# Downloader.net
KiCad netlist of a schematic drawn in Altium Designer
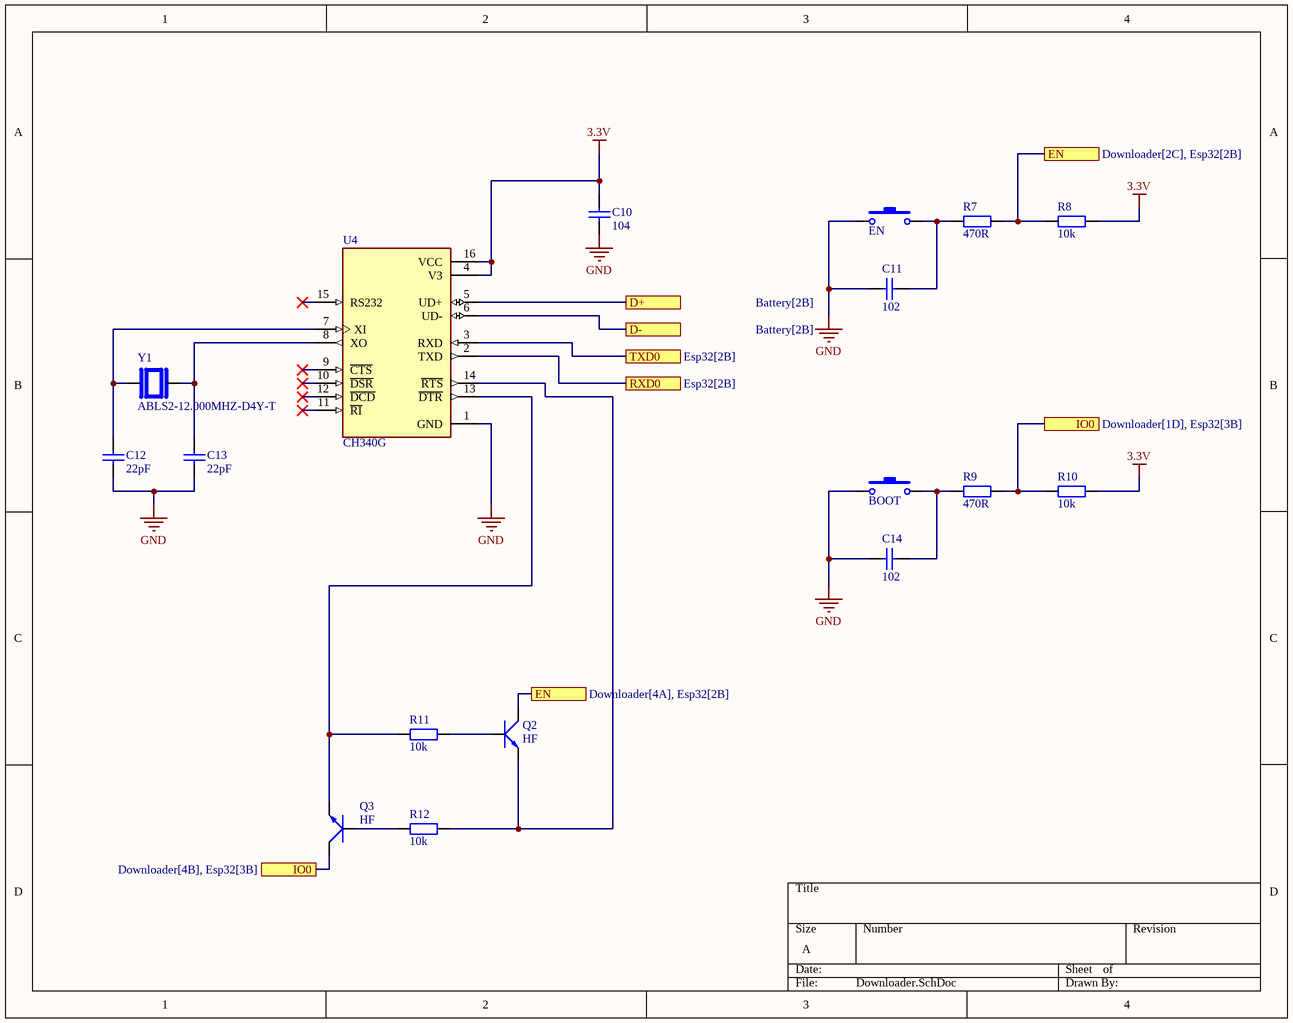
[diagram p0: Downloader.SchDoc]

(export (version "E")
  (design (tool "Eeschema 10.0.6"))
  (components
    (comp (ref "BOOT")
      (value "Nut Nhan 2 Chan SMD 3x6x2.5")
      (footprint "Nut Nhan 2 Chan SMD 3x6x2.5")
      (libsource (lib "Altium_Lib_by_KhueNguyenCreator") (part "Nut Nhan 2 Chan SMD 3x6x2.5"))
    )
    (comp (ref "C10")
      (value "104")
      (footprint "tu 0805")
      (description "Dán")
      (libsource (lib "Altium_Lib_by_KhueNguyenCreator") (part "Tu 0805 104 50V 10%"))
    )
    (comp (ref "C11")
      (value "102")
      (footprint "tu 0805")
      (description "Dán")
      (libsource (lib "Altium_Lib_by_KhueNguyenCreator") (part "Tu 0805 102 50V 10%"))
    )
    (comp (ref "C12")
      (value "22pF")
      (footprint "tu 0805")
      (description "Dán")
      (libsource (lib "Altium_Lib_by_KhueNguyenCreator") (part "Tu 0805 22pF 50V 10%"))
    )
    (comp (ref "C13")
      (value "22pF")
      (footprint "tu 0805")
      (description "Dán")
      (libsource (lib "Altium_Lib_by_KhueNguyenCreator") (part "Tu 0805 22pF 50V 10%"))
    )
    (comp (ref "C14")
      (value "102")
      (footprint "tu 0805")
      (description "Dán")
      (libsource (lib "Altium_Lib_by_KhueNguyenCreator") (part "Tu 0805 102 50V 10%"))
    )
    (comp (ref "EN")
      (value "Nut Nhan 2 Chan SMD 3x6x2.5")
      (footprint "Nut Nhan 2 Chan SMD 3x6x2.5")
      (libsource (lib "Altium_Lib_by_KhueNguyenCreator") (part "Nut Nhan 2 Chan SMD 3x6x2.5"))
    )
    (comp (ref "Q2")
      (value "HF")
      (footprint "SOT-23")
      (description "SOT-23")
      (libsource (lib "Altium_Lib_by_KhueNguyenCreator") (part "Trans C1815 HF SMD"))
    )
    (comp (ref "Q3")
      (value "HF")
      (footprint "SOT-23")
      (description "SOT-23")
      (libsource (lib "Altium_Lib_by_KhueNguyenCreator") (part "Trans C1815 HF SMD"))
    )
    (comp (ref "R7")
      (value "470R")
      (footprint "Tro SMD 0805")
      (description "Dán")
      (libsource (lib "Altium_Lib_by_KhueNguyenCreator") (part "Tro 0805 5% 470R"))
    )
    (comp (ref "R8")
      (value "10k")
      (footprint "tro smd 0805")
      (description "Dán")
      (libsource (lib "Altium_Lib_by_KhueNguyenCreator") (part "Tro 0805 5% 10k"))
    )
    (comp (ref "R9")
      (value "470R")
      (footprint "Tro SMD 0805")
      (description "Dán")
      (libsource (lib "Altium_Lib_by_KhueNguyenCreator") (part "Tro 0805 5% 470R"))
    )
    (comp (ref "R10")
      (value "10k")
      (footprint "tro smd 0805")
      (description "Dán")
      (libsource (lib "Altium_Lib_by_KhueNguyenCreator") (part "Tro 0805 5% 10k"))
    )
    (comp (ref "R11")
      (value "10k")
      (footprint "tro smd 0805")
      (description "Dán")
      (libsource (lib "Altium_Lib_by_KhueNguyenCreator") (part "Tro 0805 5% 10k"))
    )
    (comp (ref "R12")
      (value "10k")
      (footprint "tro smd 0805")
      (description "Dán")
      (libsource (lib "Altium_Lib_by_KhueNguyenCreator") (part "Tro 0805 5% 10k"))
    )
    (comp (ref "U4")
      (value "CH340G")
      (footprint "SOIC127P600X180-16N")
      (description "USB Interface Integrated Circuit")
      (fields (field (name "MP") "Ch340G") (field (name "MF") "WCH"))
      (libsource (lib "CH340G") (part "CH340G"))
    )
    (comp (ref "Y1")
      (value "ABLS2-12.000MHZ-D4Y-T")
      (footprint "XTAL_ABLS2-12.000MHZ-D4Y-T")
      (description "HC/49US (AT49) LOW PROFILE SURFACE MOUNT MICROPROCESSOR CRYSTAL")
      (fields (field (name "MF") "Abracon"))
      (libsource (lib "ABLS2-12.000MHZ-D4Y-T") (part "ABLS2-12.000MHZ-D4Y-T"))
    )
  )
  (nets
    (net (code "1") (name "/D+") (class "Default")
      (node (ref "U4") (pin "5") (pinfunction "UD+_5") (pintype "bidirectional"))
    )
    (net (code "2") (name "/D-") (class "Default")
      (node (ref "U4") (pin "6") (pinfunction "UD-_6") (pintype "bidirectional"))
    )
    (net (code "3") (name "/EN") (class "Default")
      (node (ref "Q2") (pin "3") (pinfunction "C_3") (pintype "passive"))
      (node (ref "R7") (pin "2") (pinfunction "2_2") (pintype "passive"))
      (node (ref "R8") (pin "1") (pinfunction "1_1") (pintype "passive"))
    )
    (net (code "4") (name "/IO0") (class "Default")
      (node (ref "Q3") (pin "3") (pinfunction "C_3") (pintype "passive"))
      (node (ref "R10") (pin "1") (pinfunction "1_1") (pintype "passive"))
      (node (ref "R9") (pin "2") (pinfunction "2_2") (pintype "passive"))
    )
    (net (code "5") (name "/RXD0") (class "Default")
      (node (ref "U4") (pin "2") (pinfunction "TXD_2") (pintype "output"))
    )
    (net (code "6") (name "/TXD0") (class "Default")
      (node (ref "U4") (pin "3") (pinfunction "RXD_3") (pintype "input"))
    )
    (net (code "7") (name "3.3V") (class "Default")
      (node (ref "C10") (pin "1") (pinfunction "1_1") (pintype "passive"))
      (node (ref "R10") (pin "2") (pinfunction "2_2") (pintype "passive"))
      (node (ref "R8") (pin "2") (pinfunction "2_2") (pintype "passive"))
      (node (ref "U4") (pin "16") (pinfunction "VCC_16") (pintype "power_in"))
      (node (ref "U4") (pin "4") (pinfunction "V3_4") (pintype "power_in"))
    )
    (net (code "8") (name "GND") (class "Default")
      (node (ref "BOOT") (pin "1") (pinfunction "1_1") (pintype "passive"))
      (node (ref "C10") (pin "2") (pinfunction "2_2") (pintype "passive"))
      (node (ref "C11") (pin "2") (pinfunction "2_2") (pintype "passive"))
      (node (ref "C12") (pin "2") (pinfunction "2_2") (pintype "passive"))
      (node (ref "C13") (pin "2") (pinfunction "2_2") (pintype "passive"))
      (node (ref "C14") (pin "2") (pinfunction "2_2") (pintype "passive"))
      (node (ref "EN") (pin "1") (pinfunction "1_1") (pintype "passive"))
      (node (ref "U4") (pin "1") (pinfunction "GND_1") (pintype "power_in"))
    )
    (net (code "9") (name "Net-(BOOT-Pad2)") (class "Default")
      (node (ref "BOOT") (pin "2") (pinfunction "2_2") (pintype "passive"))
      (node (ref "C14") (pin "1") (pinfunction "1_1") (pintype "passive"))
      (node (ref "R9") (pin "1") (pinfunction "1_1") (pintype "passive"))
    )
    (net (code "10") (name "Net-(C11-Pad1)") (class "Default")
      (node (ref "C11") (pin "1") (pinfunction "1_1") (pintype "passive"))
      (node (ref "EN") (pin "2") (pinfunction "2_2") (pintype "passive"))
      (node (ref "R7") (pin "1") (pinfunction "1_1") (pintype "passive"))
    )
    (net (code "11") (name "Net-(Q2-B)") (class "Default")
      (node (ref "Q2") (pin "1") (pinfunction "B_1") (pintype "passive"))
      (node (ref "R11") (pin "2") (pinfunction "2_2") (pintype "passive"))
    )
    (net (code "12") (name "Net-(Q2-E)") (class "Default")
      (node (ref "Q2") (pin "2") (pinfunction "E_2") (pintype "passive"))
      (node (ref "R12") (pin "2") (pinfunction "2_2") (pintype "passive"))
      (node (ref "U4") (pin "14") (pinfunction "~{RTS}_14") (pintype "output"))
    )
    (net (code "13") (name "Net-(Q3-B)") (class "Default")
      (node (ref "Q3") (pin "1") (pinfunction "B_1") (pintype "passive"))
      (node (ref "R12") (pin "1") (pinfunction "1_1") (pintype "passive"))
    )
    (net (code "14") (name "Net-(Q3-E)") (class "Default")
      (node (ref "Q3") (pin "2") (pinfunction "E_2") (pintype "passive"))
      (node (ref "R11") (pin "1") (pinfunction "1_1") (pintype "passive"))
      (node (ref "U4") (pin "13") (pinfunction "~{DTR}_13") (pintype "output"))
    )
    (net (code "15") (name "Net-(U4-XI)") (class "Default")
      (node (ref "C12") (pin "1") (pinfunction "1_1") (pintype "passive"))
      (node (ref "U4") (pin "7") (pinfunction "XI_7") (pintype "input"))
      (node (ref "Y1") (pin "1") (pinfunction "1_1") (pintype "passive"))
    )
    (net (code "16") (name "Net-(U4-XO)") (class "Default")
      (node (ref "C13") (pin "1") (pinfunction "1_1") (pintype "passive"))
      (node (ref "U4") (pin "8") (pinfunction "XO_8") (pintype "output"))
      (node (ref "Y1") (pin "2") (pinfunction "2_2") (pintype "passive"))
    )
    (net (code "17") (name "unconnected-(U4-RS232-Pad15)") (class "Default")
      (node (ref "U4") (pin "15") (pinfunction "RS232_15") (pintype "input+no_connect"))
    )
    (net (code "18") (name "unconnected-(U4-~{CTS}-Pad9)") (class "Default")
      (node (ref "U4") (pin "9") (pinfunction "~{CTS}_9") (pintype "input+no_connect"))
    )
    (net (code "19") (name "unconnected-(U4-~{DCD}-Pad12)") (class "Default")
      (node (ref "U4") (pin "12") (pinfunction "~{DCD}_12") (pintype "input+no_connect"))
    )
    (net (code "20") (name "unconnected-(U4-~{DSR}-Pad10)") (class "Default")
      (node (ref "U4") (pin "10") (pinfunction "~{DSR}_10") (pintype "input+no_connect"))
    )
    (net (code "21") (name "unconnected-(U4-~{RI}-Pad11)") (class "Default")
      (node (ref "U4") (pin "11") (pinfunction "~{RI}_11") (pintype "input+no_connect"))
    )
  )
)
